# PLWD_LTE_SIM.net
KiCad netlist of a schematic drawn in Altium Designer
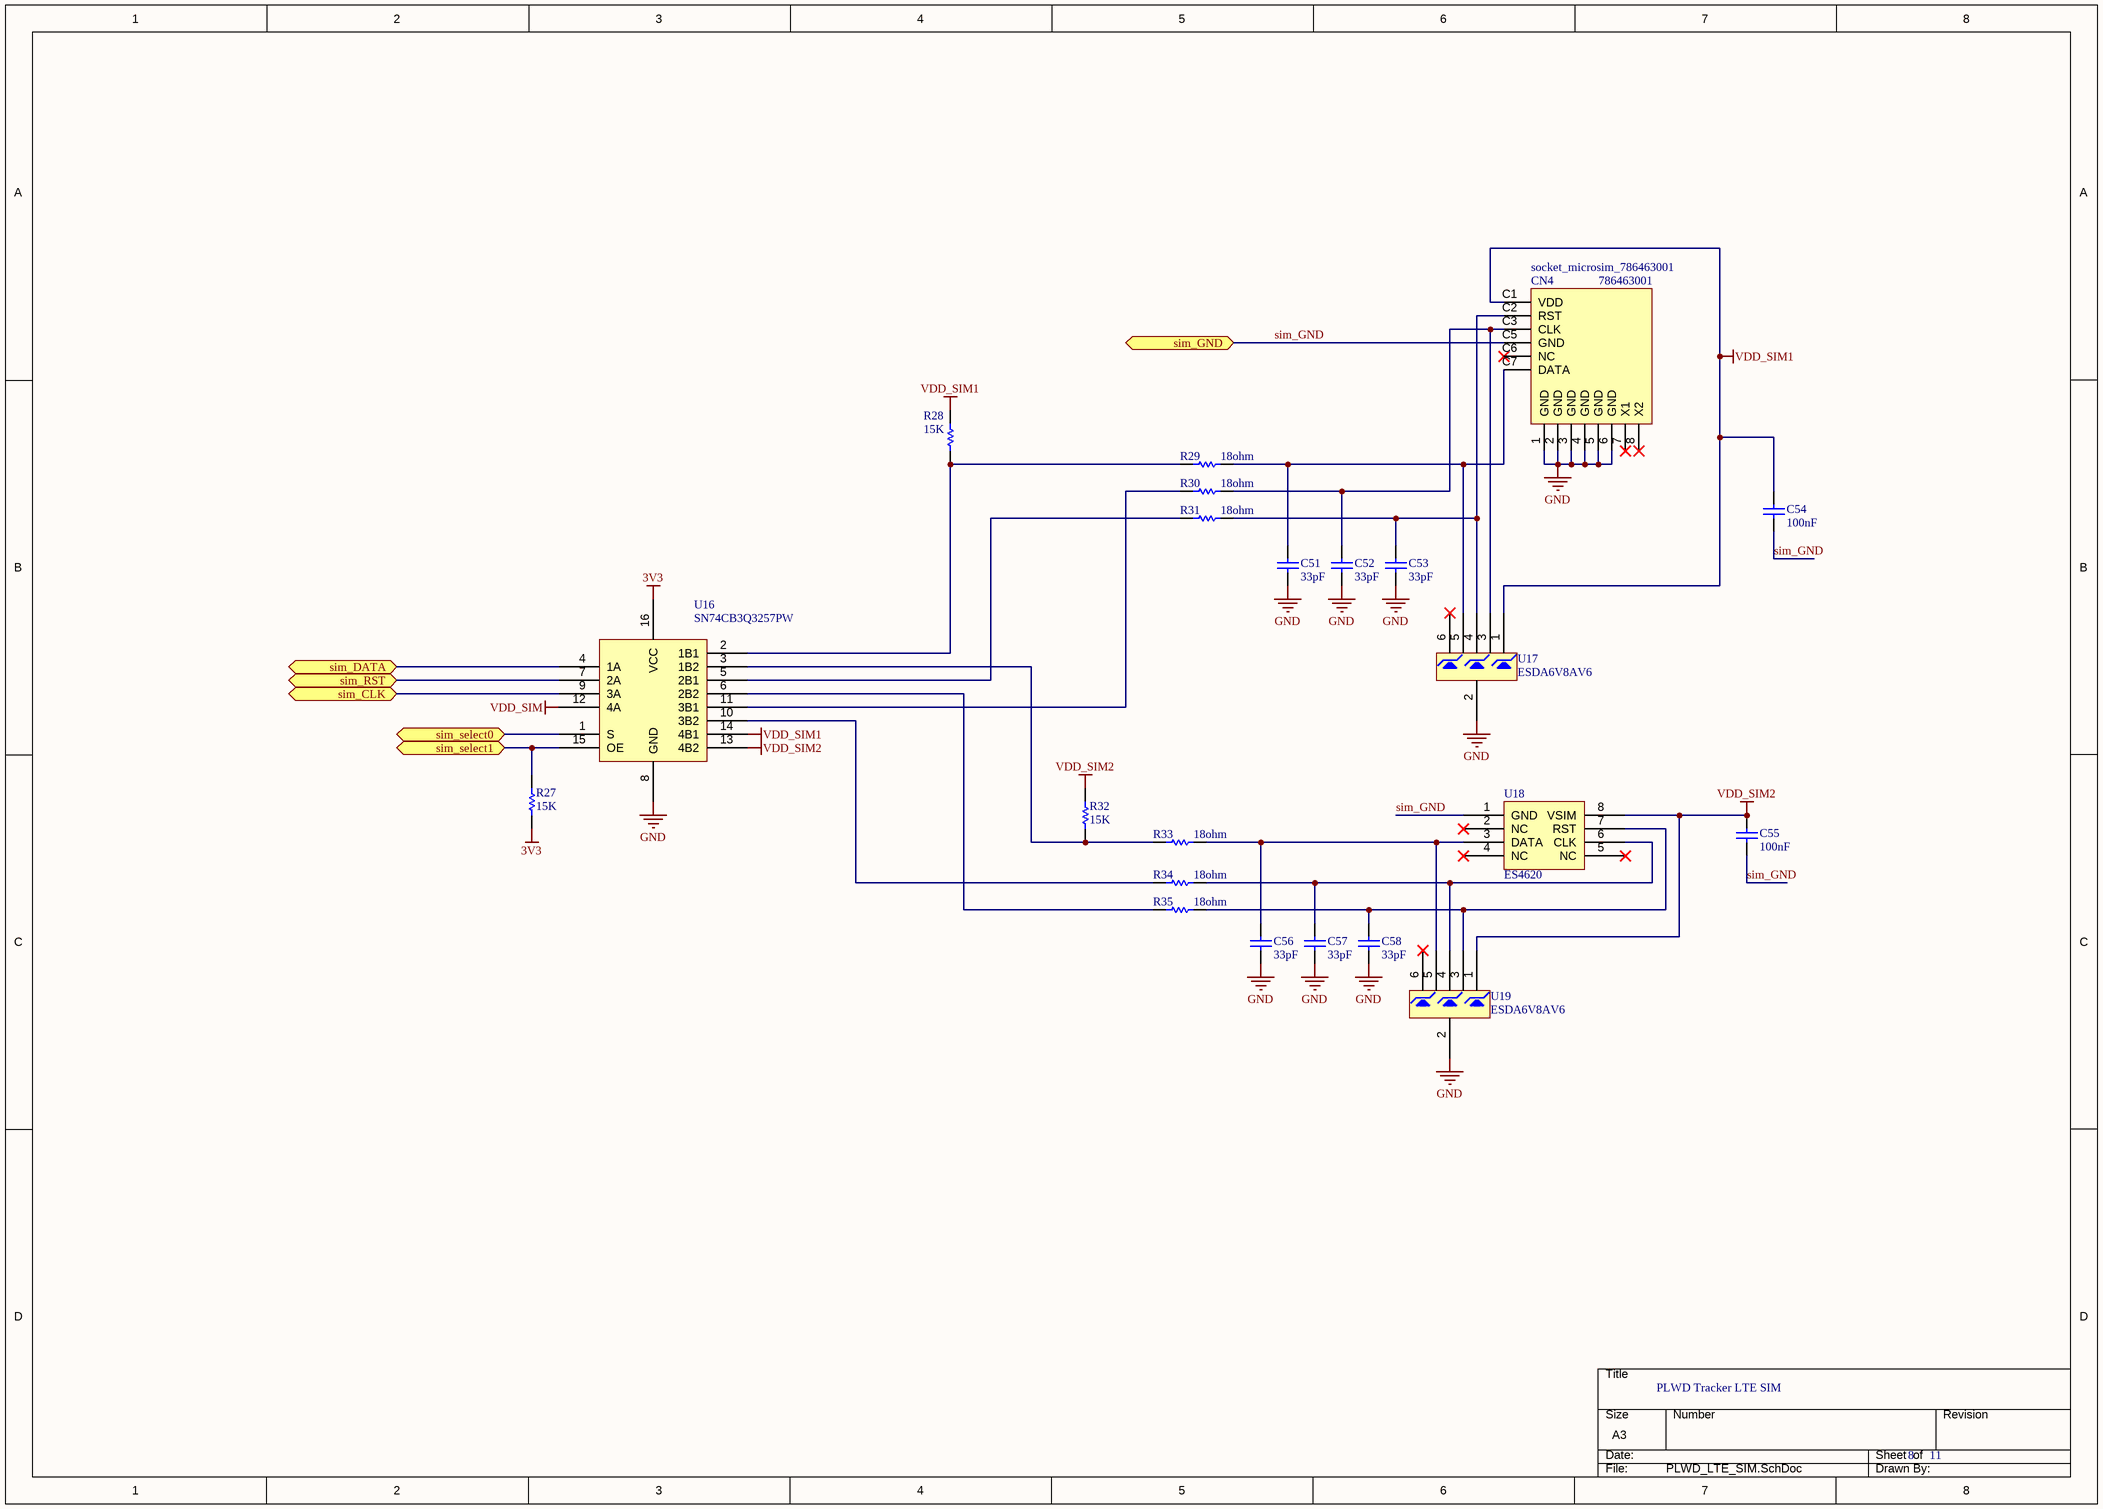
[diagram p0: PLWD_LTE_SIM.SchDoc]

(export (version "E")
  (design (tool "Eeschema 10.0.6"))
  (components
    (comp (ref "C51")
      (value "33pF")
      (footprint "C0402")
      (description "capacitor 33pF 50V 5% 0402 COG YAGEO")
      (fields
        (field (name "INTERNAL_PART_NUMBER") "MCD-00277")
        (field (name "MANUFACTURER_PART_NUMBER") "CC0402JRNPO9BN330")
        (field (name "PROVIDED_BY") "Subcon")
      )
      (libsource (lib "MCD_PARTS_database") (part "Capacitor"))
    )
    (comp (ref "C52")
      (value "33pF")
      (footprint "C0402")
      (description "capacitor 33pF 50V 5% 0402 COG YAGEO")
      (fields
        (field (name "INTERNAL_PART_NUMBER") "MCD-00277")
        (field (name "MANUFACTURER_PART_NUMBER") "CC0402JRNPO9BN330")
        (field (name "PROVIDED_BY") "Subcon")
      )
      (libsource (lib "MCD_PARTS_database") (part "Capacitor"))
    )
    (comp (ref "C53")
      (value "33pF")
      (footprint "C0402")
      (description "capacitor 33pF 50V 5% 0402 COG YAGEO")
      (fields
        (field (name "INTERNAL_PART_NUMBER") "MCD-00277")
        (field (name "MANUFACTURER_PART_NUMBER") "CC0402JRNPO9BN330")
        (field (name "PROVIDED_BY") "Subcon")
      )
      (libsource (lib "MCD_PARTS_database") (part "Capacitor"))
    )
    (comp (ref "C54")
      (value "100nF")
      (footprint "C0402")
      (description "Capacitor,100nF,16V,X7R,10%,0402,YAGEO")
      (fields
        (field (name "INTERNAL_PART_NUMBER") "MCD-00006")
        (field (name "MANUFACTURER_PART_NUMBER") "CC0402KRX7R7BB104")
        (field (name "PROVIDED_BY") "Subcon")
      )
      (libsource (lib "MCD_PARTS_database") (part "Capacitor"))
    )
    (comp (ref "C55")
      (value "100nF")
      (footprint "C0402")
      (description "Capacitor,100nF,16V,X7R,10%,0402,YAGEO")
      (fields
        (field (name "INTERNAL_PART_NUMBER") "MCD-00006")
        (field (name "MANUFACTURER_PART_NUMBER") "CC0402KRX7R7BB104")
        (field (name "PROVIDED_BY") "Subcon")
      )
      (libsource (lib "MCD_PARTS_database") (part "Capacitor"))
    )
    (comp (ref "C56")
      (value "33pF")
      (footprint "C0402")
      (description "capacitor 33pF 50V 5% 0402 COG YAGEO")
      (fields
        (field (name "INTERNAL_PART_NUMBER") "MCD-00277")
        (field (name "MANUFACTURER_PART_NUMBER") "CC0402JRNPO9BN330")
        (field (name "PROVIDED_BY") "Subcon")
      )
      (libsource (lib "MCD_PARTS_database") (part "Capacitor"))
    )
    (comp (ref "C57")
      (value "33pF")
      (footprint "C0402")
      (description "capacitor 33pF 50V 5% 0402 COG YAGEO")
      (fields
        (field (name "INTERNAL_PART_NUMBER") "MCD-00277")
        (field (name "MANUFACTURER_PART_NUMBER") "CC0402JRNPO9BN330")
        (field (name "PROVIDED_BY") "Subcon")
      )
      (libsource (lib "MCD_PARTS_database") (part "Capacitor"))
    )
    (comp (ref "C58")
      (value "33pF")
      (footprint "C0402")
      (description "capacitor 33pF 50V 5% 0402 COG YAGEO")
      (fields
        (field (name "INTERNAL_PART_NUMBER") "MCD-00277")
        (field (name "MANUFACTURER_PART_NUMBER") "CC0402JRNPO9BN330")
        (field (name "PROVIDED_BY") "Subcon")
      )
      (libsource (lib "MCD_PARTS_database") (part "Capacitor"))
    )
    (comp (ref "CN4")
      (value "socket_microsim_786463001")
      (footprint "CON_MICRO-SIMCARD_MOLEX_SD-78646-3001")
      (description "Socket_microsim 16*13, height 1.45mm")
      (fields
        (field (name "INTERNAL_PART_NUMBER") "MCD-01019")
        (field (name "ALTIUM_VALUE") "786463001")
        (field (name "MANUFACTURER_PART_NUMBER") "786463001")
        (field (name "PROVIDED_BY") "Subcon")
      )
      (libsource (lib "MCD_PARTS_database") (part "socket_microsim_786463001"))
    )
    (comp (ref "R27")
      (value "15K")
      (footprint "R0402")
      (description "Resistor,15K,0402,5%")
      (fields
        (field (name "INTERNAL_PART_NUMBER") "MCD-00285")
        (field (name "MANUFACTURER_PART_NUMBER") "RC0402JR-0715KL")
        (field (name "PROVIDED_BY") "Subcon")
      )
      (libsource (lib "MCD_PARTS_database") (part "Resistor"))
    )
    (comp (ref "R28")
      (value "15K")
      (footprint "R0402")
      (description "resistor, 15K 0402 5%")
      (fields
        (field (name "INTERNAL_PART_NUMBER") "MCD-00285")
        (field (name "MANUFACTURER_PART_NUMBER") "RC0402JR-0715KL")
        (field (name "PROVIDED_BY") "Subcon")
      )
      (libsource (lib "MCD_PARTS_database") (part "Resistor"))
    )
    (comp (ref "R29")
      (value "18ohm")
      (footprint "R0402")
      (description "resistor, 18 0402 5%")
      (fields
        (field (name "INTERNAL_PART_NUMBER") "MCD-00286")
        (field (name "MANUFACTURER_PART_NUMBER") "RC0402jR-0718RL")
        (field (name "PROVIDED_BY") "Subcon")
      )
      (libsource (lib "MCD_PARTS_database") (part "Resistor"))
    )
    (comp (ref "R30")
      (value "18ohm")
      (footprint "R0402")
      (description "resistor, 18 0402 5%")
      (fields
        (field (name "INTERNAL_PART_NUMBER") "MCD-00286")
        (field (name "MANUFACTURER_PART_NUMBER") "RC0402jR-0718RL")
        (field (name "PROVIDED_BY") "Subcon")
      )
      (libsource (lib "MCD_PARTS_database") (part "Resistor"))
    )
    (comp (ref "R31")
      (value "18ohm")
      (footprint "R0402")
      (description "resistor, 18 0402 5%")
      (fields
        (field (name "INTERNAL_PART_NUMBER") "MCD-00286")
        (field (name "MANUFACTURER_PART_NUMBER") "RC0402jR-0718RL")
        (field (name "PROVIDED_BY") "Subcon")
      )
      (libsource (lib "MCD_PARTS_database") (part "Resistor"))
    )
    (comp (ref "R32")
      (value "15K")
      (footprint "R0402")
      (description "resistor, 15K 0402 5%")
      (fields
        (field (name "INTERNAL_PART_NUMBER") "MCD-00285")
        (field (name "MANUFACTURER_PART_NUMBER") "RC0402JR-0715KL")
        (field (name "PROVIDED_BY") "Subcon")
      )
      (libsource (lib "MCD_PARTS_database") (part "Resistor"))
    )
    (comp (ref "R33")
      (value "18ohm")
      (footprint "R0402")
      (description "resistor, 18 0402 5%")
      (fields
        (field (name "INTERNAL_PART_NUMBER") "MCD-00286")
        (field (name "MANUFACTURER_PART_NUMBER") "RC0402jR-0718RL")
        (field (name "PROVIDED_BY") "Subcon")
      )
      (libsource (lib "MCD_PARTS_database") (part "Resistor"))
    )
    (comp (ref "R34")
      (value "18ohm")
      (footprint "R0402")
      (description "resistor, 18 0402 5%")
      (fields
        (field (name "INTERNAL_PART_NUMBER") "MCD-00286")
        (field (name "MANUFACTURER_PART_NUMBER") "RC0402jR-0718RL")
        (field (name "PROVIDED_BY") "Subcon")
      )
      (libsource (lib "MCD_PARTS_database") (part "Resistor"))
    )
    (comp (ref "R35")
      (value "18ohm")
      (footprint "R0402")
      (description "resistor, 18 0402 5%")
      (fields
        (field (name "INTERNAL_PART_NUMBER") "MCD-00286")
        (field (name "MANUFACTURER_PART_NUMBER") "RC0402jR-0718RL")
        (field (name "PROVIDED_BY") "Subcon")
      )
      (libsource (lib "MCD_PARTS_database") (part "Resistor"))
    )
    (comp (ref "U16")
      (value "SN74CB3Q3257PW")
      (footprint "ICC_TSSOP16_5P1X4P5_P065")
      (description "switch multiplexer")
      (fields
        (field (name "INTERNAL_PART_NUMBER") "MCD-00287")
        (field (name "MANUFACTURER") "TEXAS INSTRUMENTS")
        (field (name "PROVIDED_BY") "Subcon")
      )
      (libsource (lib "MCD_PARTS_database") (part "SN74CB3Q3257PW"))
    )
    (comp (ref "U17")
      (value "ESDA6V8AV6")
      (footprint "ESD_SOT563-6L_P050")
      (description "ESD protection")
      (fields
        (field (name "INTERNAL_PART_NUMBER") "MCD-00282")
        (field (name "MANUFACTURER") "WILLSEMI")
        (field (name "PROVIDED_BY") "Subcon")
      )
      (libsource (lib "MCD_PARTS_database") (part "ESDA6V8AV6"))
    )
    (comp (ref "U18")
      (value "ES4620")
      (footprint "CON_SIMCARD_ESEYE_ES4620")
      (description "embedded SIM")
      (fields
        (field (name "INTERNAL_PART_NUMBER") "MCD-00281")
        (field (name "MANUFACTURER") "ESEYE")
        (field (name "PROVIDED_BY") "Subcon")
      )
      (libsource (lib "MCD_PARTS_database") (part "ES4620"))
    )
    (comp (ref "U19")
      (value "ESDA6V8AV6")
      (footprint "ESD_SOT563-6L_P050")
      (description "ESD protection")
      (fields
        (field (name "INTERNAL_PART_NUMBER") "MCD-00282")
        (field (name "MANUFACTURER") "WILLSEMI")
        (field (name "PROVIDED_BY") "Subcon")
      )
      (libsource (lib "MCD_PARTS_database") (part "ESDA6V8AV6"))
    )
  )
  (nets
    (net (code "1") (name "/sim_CLK") (class "Default")
      (node (ref "U16") (pin "9") (pinfunction "3A_9") (pintype "passive"))
    )
    (net (code "2") (name "/sim_DATA") (class "Default")
      (node (ref "U16") (pin "4") (pinfunction "1A_4") (pintype "passive"))
    )
    (net (code "3") (name "/sim_GND") (class "Default")
      (node (ref "C54") (pin "1") (pinfunction "1_1") (pintype "passive"))
      (node (ref "C55") (pin "1") (pinfunction "1_1") (pintype "passive"))
      (node (ref "CN4") (pin "C5") (pinfunction "GND_C5") (pintype "passive"))
      (node (ref "U18") (pin "1") (pinfunction "GND_1") (pintype "passive"))
    )
    (net (code "4") (name "/sim_RST") (class "Default")
      (node (ref "U16") (pin "7") (pinfunction "2A_7") (pintype "passive"))
    )
    (net (code "5") (name "/sim_select0") (class "Default")
      (node (ref "U16") (pin "1") (pinfunction "S_1") (pintype "passive"))
    )
    (net (code "6") (name "/sim_select1") (class "Default")
      (node (ref "R27") (pin "2") (pinfunction "2_2") (pintype "passive"))
      (node (ref "U16") (pin "15") (pinfunction "OE_15") (pintype "passive"))
    )
    (net (code "7") (name "3V3") (class "Default")
      (node (ref "R27") (pin "1") (pinfunction "1_1") (pintype "passive"))
      (node (ref "U16") (pin "16") (pinfunction "VCC_16") (pintype "passive"))
    )
    (net (code "8") (name "GND") (class "Default")
      (node (ref "C51") (pin "1") (pinfunction "1_1") (pintype "passive"))
      (node (ref "C52") (pin "1") (pinfunction "1_1") (pintype "passive"))
      (node (ref "C53") (pin "1") (pinfunction "1_1") (pintype "passive"))
      (node (ref "C56") (pin "1") (pinfunction "1_1") (pintype "passive"))
      (node (ref "C57") (pin "1") (pinfunction "1_1") (pintype "passive"))
      (node (ref "C58") (pin "1") (pinfunction "1_1") (pintype "passive"))
      (node (ref "CN4") (pin "1") (pinfunction "GND_1") (pintype "passive"))
      (node (ref "CN4") (pin "2") (pinfunction "GND_2") (pintype "passive"))
      (node (ref "CN4") (pin "3") (pinfunction "GND_3") (pintype "passive"))
      (node (ref "CN4") (pin "4") (pinfunction "GND_4") (pintype "passive"))
      (node (ref "CN4") (pin "5") (pinfunction "GND_5") (pintype "passive"))
      (node (ref "CN4") (pin "6") (pinfunction "GND_6") (pintype "passive"))
      (node (ref "U16") (pin "8") (pinfunction "GND_8") (pintype "passive"))
      (node (ref "U17") (pin "2") (pintype "passive"))
      (node (ref "U19") (pin "2") (pintype "passive"))
    )
    (net (code "9") (name "Net-(CN4-CLK)") (class "Default")
      (node (ref "C52") (pin "2") (pinfunction "2_2") (pintype "passive"))
      (node (ref "CN4") (pin "C3") (pinfunction "CLK_C3") (pintype "passive"))
      (node (ref "R30") (pin "2") (pinfunction "2_2") (pintype "passive"))
      (node (ref "U17") (pin "3") (pintype "passive"))
    )
    (net (code "10") (name "Net-(CN4-DATA)") (class "Default")
      (node (ref "C51") (pin "2") (pinfunction "2_2") (pintype "passive"))
      (node (ref "CN4") (pin "C7") (pinfunction "DATA_C7") (pintype "passive"))
      (node (ref "R29") (pin "2") (pinfunction "2_2") (pintype "passive"))
      (node (ref "U17") (pin "5") (pintype "passive"))
    )
    (net (code "11") (name "Net-(CN4-RST)") (class "Default")
      (node (ref "C53") (pin "2") (pinfunction "2_2") (pintype "passive"))
      (node (ref "CN4") (pin "C2") (pinfunction "RST_C2") (pintype "passive"))
      (node (ref "R31") (pin "2") (pinfunction "2_2") (pintype "passive"))
      (node (ref "U17") (pin "4") (pintype "passive"))
    )
    (net (code "12") (name "Net-(U16-1B1)") (class "Default")
      (node (ref "R28") (pin "1") (pinfunction "1_1") (pintype "passive"))
      (node (ref "R29") (pin "1") (pinfunction "1_1") (pintype "passive"))
      (node (ref "U16") (pin "2") (pinfunction "1B1_2") (pintype "passive"))
    )
    (net (code "13") (name "Net-(U16-1B2)") (class "Default")
      (node (ref "R32") (pin "1") (pinfunction "1_1") (pintype "passive"))
      (node (ref "R33") (pin "1") (pinfunction "1_1") (pintype "passive"))
      (node (ref "U16") (pin "3") (pinfunction "1B2_3") (pintype "passive"))
    )
    (net (code "14") (name "Net-(U16-2B1)") (class "Default")
      (node (ref "R31") (pin "1") (pinfunction "1_1") (pintype "passive"))
      (node (ref "U16") (pin "5") (pinfunction "2B1_5") (pintype "passive"))
    )
    (net (code "15") (name "Net-(U16-2B2)") (class "Default")
      (node (ref "R35") (pin "1") (pinfunction "1_1") (pintype "passive"))
      (node (ref "U16") (pin "6") (pinfunction "2B2_6") (pintype "passive"))
    )
    (net (code "16") (name "Net-(U16-3B1)") (class "Default")
      (node (ref "R30") (pin "1") (pinfunction "1_1") (pintype "passive"))
      (node (ref "U16") (pin "11") (pinfunction "3B1_11") (pintype "passive"))
    )
    (net (code "17") (name "Net-(U16-3B2)") (class "Default")
      (node (ref "R34") (pin "1") (pinfunction "1_1") (pintype "passive"))
      (node (ref "U16") (pin "10") (pinfunction "3B2_10") (pintype "passive"))
    )
    (net (code "18") (name "Net-(U18-CLK)") (class "Default")
      (node (ref "C57") (pin "2") (pinfunction "2_2") (pintype "passive"))
      (node (ref "R34") (pin "2") (pinfunction "2_2") (pintype "passive"))
      (node (ref "U18") (pin "6") (pinfunction "CLK_6") (pintype "passive"))
      (node (ref "U19") (pin "4") (pintype "passive"))
    )
    (net (code "19") (name "Net-(U18-DATA)") (class "Default")
      (node (ref "C56") (pin "2") (pinfunction "2_2") (pintype "passive"))
      (node (ref "R33") (pin "2") (pinfunction "2_2") (pintype "passive"))
      (node (ref "U18") (pin "3") (pinfunction "DATA_3") (pintype "passive"))
      (node (ref "U19") (pin "5") (pintype "passive"))
    )
    (net (code "20") (name "Net-(U18-RST)") (class "Default")
      (node (ref "C58") (pin "2") (pinfunction "2_2") (pintype "passive"))
      (node (ref "R35") (pin "2") (pinfunction "2_2") (pintype "passive"))
      (node (ref "U18") (pin "7") (pinfunction "RST_7") (pintype "passive"))
      (node (ref "U19") (pin "3") (pintype "passive"))
    )
    (net (code "21") (name "VDD_SIM") (class "Default")
      (node (ref "U16") (pin "12") (pinfunction "4A_12") (pintype "passive"))
    )
    (net (code "22") (name "VDD_SIM1") (class "Default")
      (node (ref "C54") (pin "2") (pinfunction "2_2") (pintype "passive"))
      (node (ref "CN4") (pin "C1") (pinfunction "VDD_C1") (pintype "passive"))
      (node (ref "R28") (pin "2") (pinfunction "2_2") (pintype "passive"))
      (node (ref "U16") (pin "14") (pinfunction "4B1_14") (pintype "passive"))
      (node (ref "U17") (pin "1") (pintype "passive"))
    )
    (net (code "23") (name "VDD_SIM2") (class "Default")
      (node (ref "C55") (pin "2") (pinfunction "2_2") (pintype "passive"))
      (node (ref "R32") (pin "2") (pinfunction "2_2") (pintype "passive"))
      (node (ref "U16") (pin "13") (pinfunction "4B2_13") (pintype "passive"))
      (node (ref "U18") (pin "8") (pinfunction "VSIM_8") (pintype "passive"))
      (node (ref "U19") (pin "1") (pintype "passive"))
    )
    (net (code "24") (name "unconnected-(CN4-NC-PadC6)") (class "Default")
      (node (ref "CN4") (pin "C6") (pinfunction "NC_C6") (pintype "passive+no_connect"))
    )
    (net (code "25") (name "unconnected-(CN4-X1-Pad7)") (class "Default")
      (node (ref "CN4") (pin "7") (pinfunction "X1_7") (pintype "passive+no_connect"))
    )
    (net (code "26") (name "unconnected-(CN4-X2-Pad8)") (class "Default")
      (node (ref "CN4") (pin "8") (pinfunction "X2_8") (pintype "passive+no_connect"))
    )
    (net (code "27") (name "unconnected-(U17-Pad6)") (class "Default")
      (node (ref "U17") (pin "6") (pintype "passive+no_connect"))
    )
    (net (code "28") (name "unconnected-(U18-NC-Pad2)") (class "Default")
      (node (ref "U18") (pin "2") (pinfunction "NC_2") (pintype "passive+no_connect"))
    )
    (net (code "29") (name "unconnected-(U18-NC-Pad4)") (class "Default")
      (node (ref "U18") (pin "4") (pinfunction "NC_4") (pintype "passive+no_connect"))
    )
    (net (code "30") (name "unconnected-(U18-NC-Pad5)") (class "Default")
      (node (ref "U18") (pin "5") (pinfunction "NC_5") (pintype "passive+no_connect"))
    )
    (net (code "31") (name "unconnected-(U19-Pad6)") (class "Default")
      (node (ref "U19") (pin "6") (pintype "passive+no_connect"))
    )
  )
)
